# fusesBoard.net
KiCad netlist of a schematic drawn in EAGLE
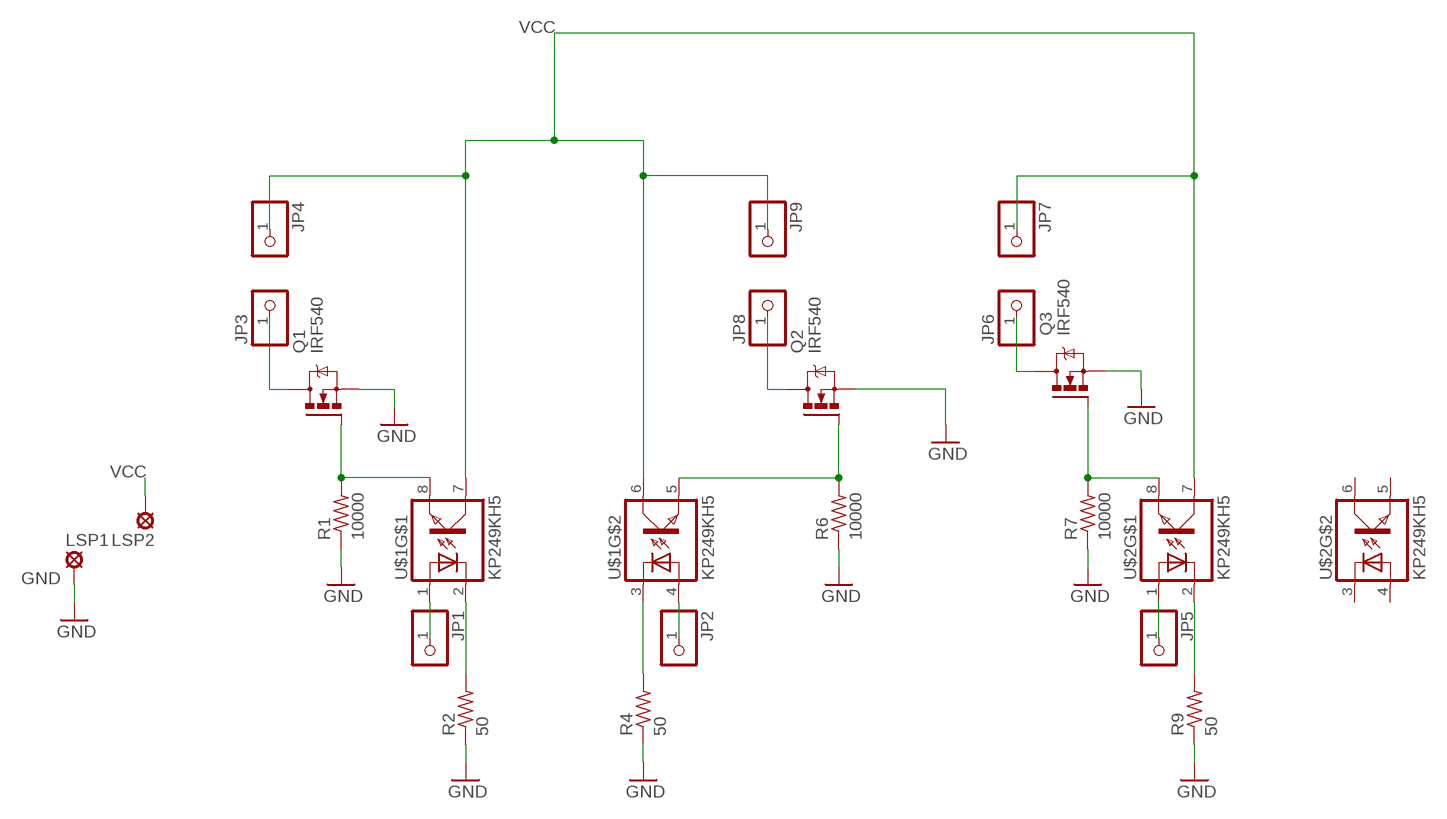
[diagram p0: schematic, sheet 1]

(export (version "E")
  (design (tool "Eeschema 10.0.6"))
  (components
    (comp (ref "JP1")
      (value "PINHD-1X1")
      (footprint "eagle-import:1X01")
      (libsource (lib "eagle-import") (part "PINHD-1X1"))
    )
    (comp (ref "JP2")
      (value "PINHD-1X1")
      (footprint "eagle-import:1X01")
      (libsource (lib "eagle-import") (part "PINHD-1X1"))
    )
    (comp (ref "JP3")
      (value "PINHD-1X1")
      (footprint "eagle-import:1X01")
      (libsource (lib "eagle-import") (part "PINHD-1X1"))
    )
    (comp (ref "JP4")
      (value "PINHD-1X1")
      (footprint "eagle-import:1X01")
      (libsource (lib "eagle-import") (part "PINHD-1X1"))
    )
    (comp (ref "JP5")
      (value "PINHD-1X1")
      (footprint "eagle-import:1X01")
      (libsource (lib "eagle-import") (part "PINHD-1X1"))
    )
    (comp (ref "JP6")
      (value "PINHD-1X1")
      (footprint "eagle-import:1X01")
      (libsource (lib "eagle-import") (part "PINHD-1X1"))
    )
    (comp (ref "JP7")
      (value "PINHD-1X1")
      (footprint "eagle-import:1X01")
      (libsource (lib "eagle-import") (part "PINHD-1X1"))
    )
    (comp (ref "JP8")
      (value "PINHD-1X1")
      (footprint "eagle-import:1X01")
      (libsource (lib "eagle-import") (part "PINHD-1X1"))
    )
    (comp (ref "JP9")
      (value "PINHD-1X1")
      (footprint "eagle-import:1X01")
      (libsource (lib "eagle-import") (part "PINHD-1X1"))
    )
    (comp (ref "LSP1")
      (value "SE14")
      (footprint "eagle-import:SE14")
      (libsource (lib "eagle-import") (part "SE14"))
    )
    (comp (ref "LSP2")
      (value "SE14")
      (footprint "eagle-import:SE14")
      (libsource (lib "eagle-import") (part "SE14"))
    )
    (comp (ref "Q1")
      (value "IRF540")
      (footprint "eagle-import:TO220BV")
      (libsource (lib "eagle-import") (part "IRF540"))
    )
    (comp (ref "Q2")
      (value "IRF540")
      (footprint "eagle-import:TO220BV")
      (libsource (lib "eagle-import") (part "IRF540"))
    )
    (comp (ref "Q3")
      (value "IRF540")
      (footprint "eagle-import:TO220BV")
      (libsource (lib "eagle-import") (part "IRF540"))
    )
    (comp (ref "R1")
      (value "10000")
      (footprint "eagle-import:0204_7")
      (libsource (lib "eagle-import") (part "R-US_0204/7"))
    )
    (comp (ref "R2")
      (value "50")
      (footprint "eagle-import:0204_7")
      (libsource (lib "eagle-import") (part "R-US_0204/7"))
    )
    (comp (ref "R4")
      (value "50")
      (footprint "eagle-import:0204_7")
      (libsource (lib "eagle-import") (part "R-US_0204/7"))
    )
    (comp (ref "R6")
      (value "10000")
      (footprint "eagle-import:0204_7")
      (libsource (lib "eagle-import") (part "R-US_0204/7"))
    )
    (comp (ref "R7")
      (value "10000")
      (footprint "eagle-import:0204_7")
      (libsource (lib "eagle-import") (part "R-US_0204/7"))
    )
    (comp (ref "R9")
      (value "50")
      (footprint "eagle-import:0204_7")
      (libsource (lib "eagle-import") (part "R-US_0204/7"))
    )
    (comp (ref "U$1")
      (value "KP249KH5")
      (footprint "eagle-import:DIL08")
      (libsource (lib "eagle-import") (part "KP249KH5"))
    )
    (comp (ref "U$2")
      (value "KP249KH5")
      (footprint "eagle-import:DIL08")
      (libsource (lib "eagle-import") (part "KP249KH5"))
    )
  )
  (nets
    (net (code "1") (name "/VCC") (class "Default")
      (node (ref "JP4") (pin "1") (pinfunction "1_1") (pintype "passive"))
      (node (ref "JP7") (pin "1") (pinfunction "1_1") (pintype "passive"))
      (node (ref "JP9") (pin "1") (pinfunction "1_1") (pintype "passive"))
      (node (ref "LSP2") (pin "MP") (pinfunction "MP_MP") (pintype "passive"))
      (node (ref "U$1") (pin "6") (pinfunction "6_6") (pintype "passive"))
      (node (ref "U$1") (pin "7") (pinfunction "7_7") (pintype "passive"))
      (node (ref "U$2") (pin "7") (pinfunction "7_7") (pintype "passive"))
    )
    (net (code "2") (name "GND") (class "Default")
      (node (ref "LSP1") (pin "MP") (pinfunction "MP_MP") (pintype "passive"))
      (node (ref "Q1") (pin "S") (pinfunction "S_S") (pintype "passive"))
      (node (ref "Q2") (pin "S") (pinfunction "S_S") (pintype "passive"))
      (node (ref "Q3") (pin "S") (pinfunction "S_S") (pintype "passive"))
      (node (ref "R1") (pin "1") (pinfunction "1_1") (pintype "passive"))
      (node (ref "R2") (pin "1") (pinfunction "1_1") (pintype "passive"))
      (node (ref "R4") (pin "1") (pinfunction "1_1") (pintype "passive"))
      (node (ref "R6") (pin "1") (pinfunction "1_1") (pintype "passive"))
      (node (ref "R7") (pin "1") (pinfunction "1_1") (pintype "passive"))
      (node (ref "R9") (pin "1") (pinfunction "1_1") (pintype "passive"))
    )
    (net (code "3") (name "Net-(JP1-Pad1)") (class "Default")
      (node (ref "JP1") (pin "1") (pinfunction "1_1") (pintype "passive"))
      (node (ref "U$1") (pin "1") (pinfunction "1_1") (pintype "passive"))
    )
    (net (code "4") (name "Net-(JP2-Pad1)") (class "Default")
      (node (ref "JP2") (pin "1") (pinfunction "1_1") (pintype "passive"))
      (node (ref "U$1") (pin "4") (pinfunction "4_4") (pintype "passive"))
    )
    (net (code "5") (name "Net-(JP3-Pad1)") (class "Default")
      (node (ref "JP3") (pin "1") (pinfunction "1_1") (pintype "passive"))
      (node (ref "Q1") (pin "D") (pinfunction "D_D") (pintype "passive"))
    )
    (net (code "6") (name "Net-(JP5-Pad1)") (class "Default")
      (node (ref "JP5") (pin "1") (pinfunction "1_1") (pintype "passive"))
      (node (ref "U$2") (pin "1") (pinfunction "1_1") (pintype "passive"))
    )
    (net (code "7") (name "Net-(JP6-Pad1)") (class "Default")
      (node (ref "JP6") (pin "1") (pinfunction "1_1") (pintype "passive"))
      (node (ref "Q3") (pin "D") (pinfunction "D_D") (pintype "passive"))
    )
    (net (code "8") (name "Net-(JP8-Pad1)") (class "Default")
      (node (ref "JP8") (pin "1") (pinfunction "1_1") (pintype "passive"))
      (node (ref "Q2") (pin "D") (pinfunction "D_D") (pintype "passive"))
    )
    (net (code "9") (name "Net-(Q1-PadG)") (class "Default")
      (node (ref "Q1") (pin "G") (pinfunction "G_G") (pintype "passive"))
      (node (ref "R1") (pin "2") (pinfunction "2_2") (pintype "passive"))
      (node (ref "U$1") (pin "8") (pinfunction "8_8") (pintype "passive"))
    )
    (net (code "10") (name "Net-(Q2-PadG)") (class "Default")
      (node (ref "Q2") (pin "G") (pinfunction "G_G") (pintype "passive"))
      (node (ref "R6") (pin "2") (pinfunction "2_2") (pintype "passive"))
      (node (ref "U$1") (pin "5") (pinfunction "5_5") (pintype "passive"))
    )
    (net (code "11") (name "Net-(Q3-PadG)") (class "Default")
      (node (ref "Q3") (pin "G") (pinfunction "G_G") (pintype "passive"))
      (node (ref "R7") (pin "2") (pinfunction "2_2") (pintype "passive"))
      (node (ref "U$2") (pin "8") (pinfunction "8_8") (pintype "passive"))
    )
    (net (code "12") (name "Net-(R2-Pad2)") (class "Default")
      (node (ref "R2") (pin "2") (pinfunction "2_2") (pintype "passive"))
      (node (ref "U$1") (pin "2") (pinfunction "2_2") (pintype "passive"))
    )
    (net (code "13") (name "Net-(R4-Pad2)") (class "Default")
      (node (ref "R4") (pin "2") (pinfunction "2_2") (pintype "passive"))
      (node (ref "U$1") (pin "3") (pinfunction "3_3") (pintype "passive"))
    )
    (net (code "14") (name "Net-(R9-Pad2)") (class "Default")
      (node (ref "R9") (pin "2") (pinfunction "2_2") (pintype "passive"))
      (node (ref "U$2") (pin "2") (pinfunction "2_2") (pintype "passive"))
    )
    (net (code "15") (name "unconnected-(U$2-Pad3)") (class "Default")
      (node (ref "U$2") (pin "3") (pinfunction "3_3") (pintype "passive"))
    )
    (net (code "16") (name "unconnected-(U$2-Pad4)") (class "Default")
      (node (ref "U$2") (pin "4") (pinfunction "4_4") (pintype "passive"))
    )
    (net (code "17") (name "unconnected-(U$2-Pad5)") (class "Default")
      (node (ref "U$2") (pin "5") (pinfunction "5_5") (pintype "passive"))
    )
    (net (code "18") (name "unconnected-(U$2-Pad6)") (class "Default")
      (node (ref "U$2") (pin "6") (pinfunction "6_6") (pintype "passive"))
    )
  )
)
